# B201E.net
KiCad netlist of a schematic drawn in EAGLE
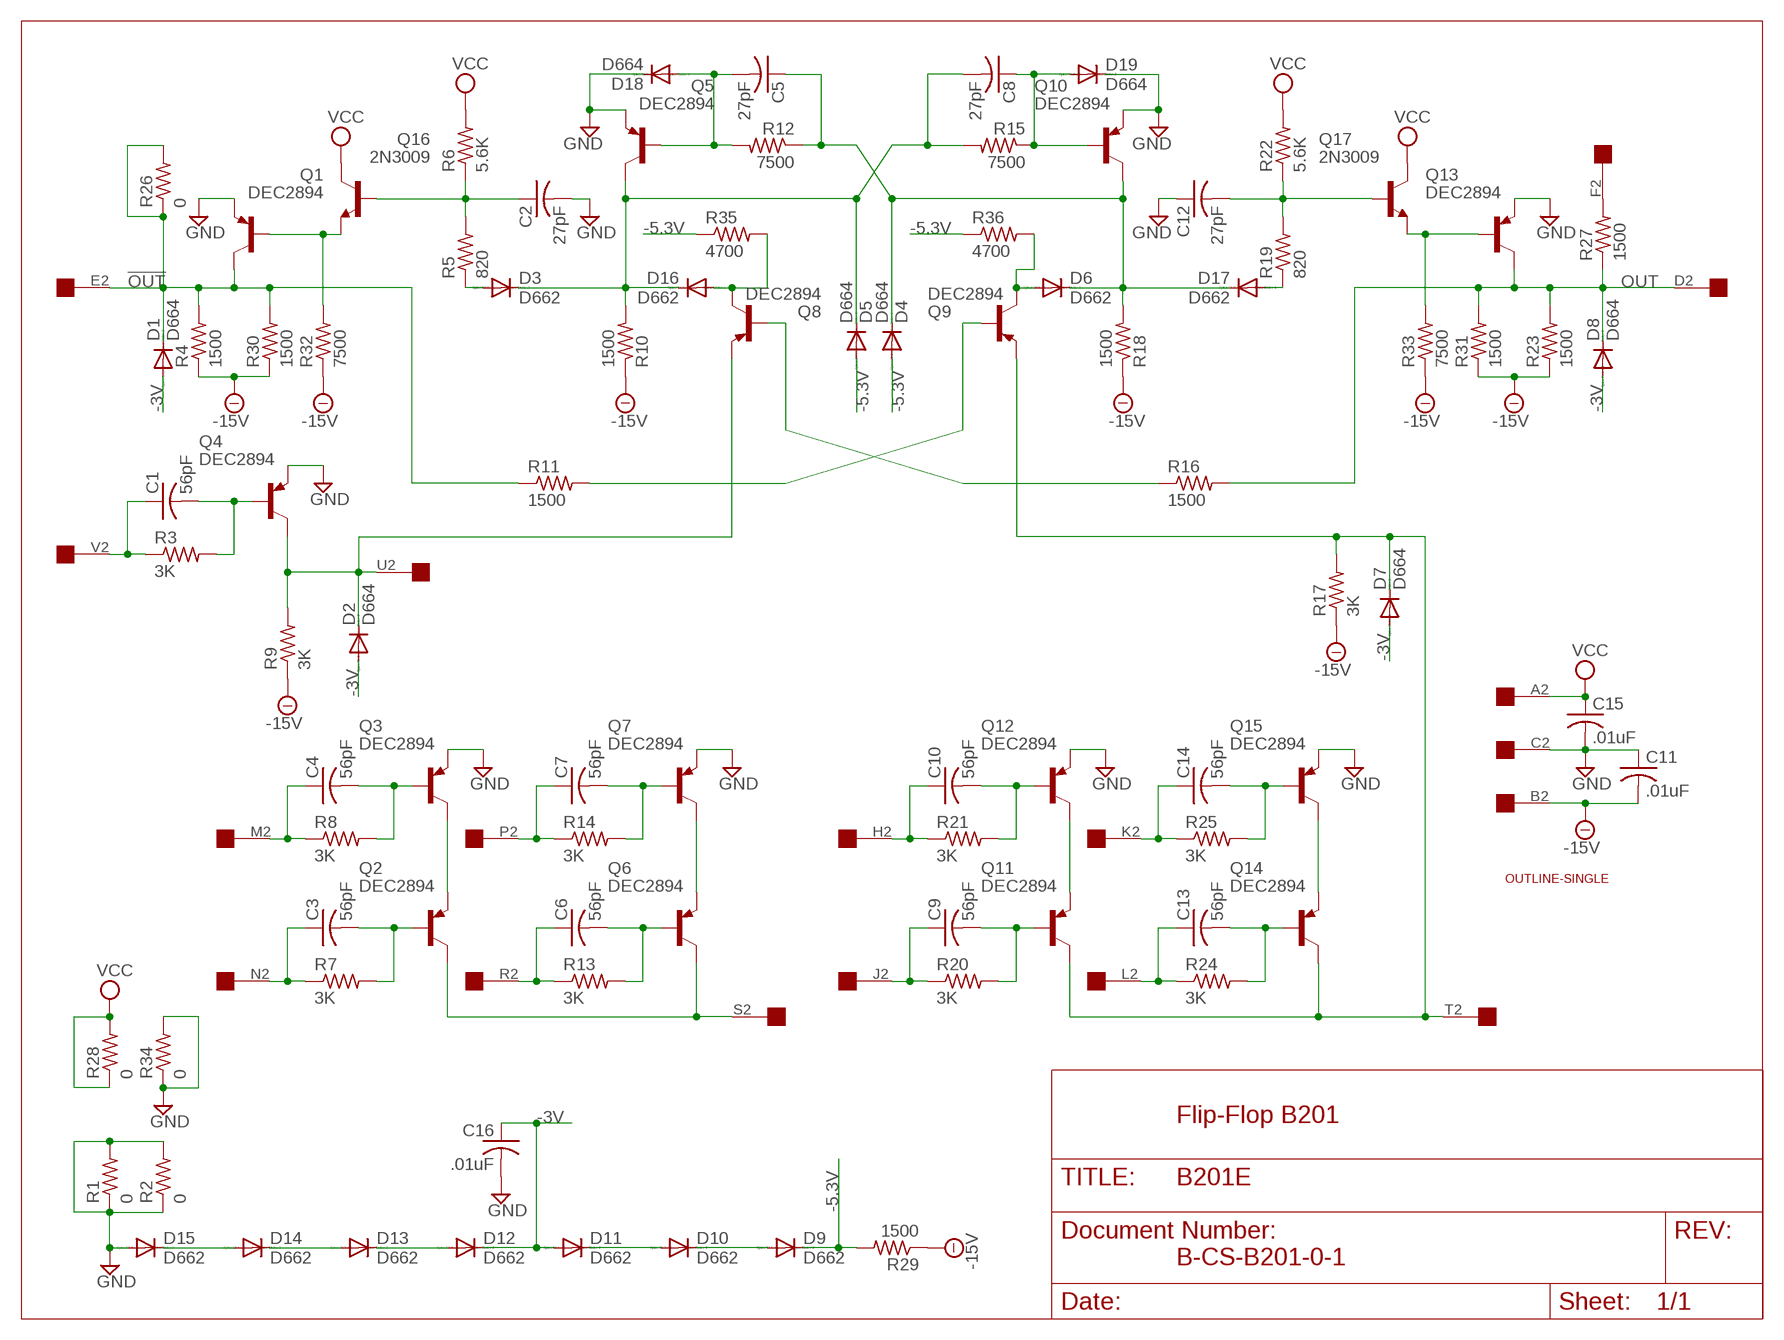
[diagram p0: schematic, sheet 1]

(export (version "E")
  (design (tool "Eeschema 10.0.6"))
  (components
    (comp (ref "C1")
      (value "56pF")
      (footprint "eagle-import:C063-025X075")
      (libsource (lib "eagle-import") (part "C-US"))
    )
    (comp (ref "C2")
      (value "27pF")
      (footprint "eagle-import:C063-025X075")
      (libsource (lib "eagle-import") (part "C-US"))
    )
    (comp (ref "C3")
      (value "56pF")
      (footprint "eagle-import:C063-025X075")
      (libsource (lib "eagle-import") (part "C-US"))
    )
    (comp (ref "C4")
      (value "56pF")
      (footprint "eagle-import:C063-025X075")
      (libsource (lib "eagle-import") (part "C-US"))
    )
    (comp (ref "C5")
      (value "27pF")
      (footprint "eagle-import:C063-025X075")
      (libsource (lib "eagle-import") (part "C-US"))
    )
    (comp (ref "C6")
      (value "56pF")
      (footprint "eagle-import:C063-025X075")
      (libsource (lib "eagle-import") (part "C-US"))
    )
    (comp (ref "C7")
      (value "56pF")
      (footprint "eagle-import:C063-025X075")
      (libsource (lib "eagle-import") (part "C-US"))
    )
    (comp (ref "C8")
      (value "27pF")
      (footprint "eagle-import:C063-025X075")
      (libsource (lib "eagle-import") (part "C-US"))
    )
    (comp (ref "C9")
      (value "56pF")
      (footprint "eagle-import:C063-025X075")
      (libsource (lib "eagle-import") (part "C-US"))
    )
    (comp (ref "C10")
      (value "56pF")
      (footprint "eagle-import:C063-025X075")
      (libsource (lib "eagle-import") (part "C-US"))
    )
    (comp (ref "C11")
      (value ".01uF")
      (footprint "eagle-import:C063-025X075")
      (libsource (lib "eagle-import") (part "C-US"))
    )
    (comp (ref "C12")
      (value "27pF")
      (footprint "eagle-import:C063-025X075")
      (libsource (lib "eagle-import") (part "C-US"))
    )
    (comp (ref "C13")
      (value "56pF")
      (footprint "eagle-import:C063-025X075")
      (libsource (lib "eagle-import") (part "C-US"))
    )
    (comp (ref "C14")
      (value "56pF")
      (footprint "eagle-import:C063-025X075")
      (libsource (lib "eagle-import") (part "C-US"))
    )
    (comp (ref "C15")
      (value ".01uF")
      (footprint "eagle-import:C063-025X075")
      (libsource (lib "eagle-import") (part "C-US"))
    )
    (comp (ref "C16")
      (value ".01uF")
      (footprint "eagle-import:C063-025X075")
      (libsource (lib "eagle-import") (part "C-US"))
    )
    (comp (ref "D1")
      (value "D664")
      (footprint "eagle-import:DO35-10")
      (libsource (lib "eagle-import") (part "DIODE-DO35-10"))
    )
    (comp (ref "D2")
      (value "D664")
      (footprint "eagle-import:DO35-10")
      (libsource (lib "eagle-import") (part "DIODE-DO35-10"))
    )
    (comp (ref "D3")
      (value "D662")
      (footprint "eagle-import:DO35-10")
      (libsource (lib "eagle-import") (part "DIODE-DO35-10"))
    )
    (comp (ref "D4")
      (value "D664")
      (footprint "eagle-import:DO35-10")
      (libsource (lib "eagle-import") (part "DIODE-DO35-10"))
    )
    (comp (ref "D5")
      (value "D664")
      (footprint "eagle-import:DO35-10")
      (libsource (lib "eagle-import") (part "DIODE-DO35-10"))
    )
    (comp (ref "D6")
      (value "D662")
      (footprint "eagle-import:DO35-10")
      (libsource (lib "eagle-import") (part "DIODE-DO35-10"))
    )
    (comp (ref "D7")
      (value "D664")
      (footprint "eagle-import:DO35-10")
      (libsource (lib "eagle-import") (part "DIODE-DO35-10"))
    )
    (comp (ref "D8")
      (value "D664")
      (footprint "eagle-import:DO35-10")
      (libsource (lib "eagle-import") (part "DIODE-DO35-10"))
    )
    (comp (ref "D9")
      (value "D662")
      (footprint "eagle-import:DO35-10")
      (libsource (lib "eagle-import") (part "DIODE-DO35-10"))
    )
    (comp (ref "D10")
      (value "D662")
      (footprint "eagle-import:DO35-10")
      (libsource (lib "eagle-import") (part "DIODE-DO35-10"))
    )
    (comp (ref "D11")
      (value "D662")
      (footprint "eagle-import:DO35-10")
      (libsource (lib "eagle-import") (part "DIODE-DO35-10"))
    )
    (comp (ref "D12")
      (value "D662")
      (footprint "eagle-import:DO35-10")
      (libsource (lib "eagle-import") (part "DIODE-DO35-10"))
    )
    (comp (ref "D13")
      (value "D662")
      (footprint "eagle-import:DO35-10")
      (libsource (lib "eagle-import") (part "DIODE-DO35-10"))
    )
    (comp (ref "D14")
      (value "D662")
      (footprint "eagle-import:DO35-10")
      (libsource (lib "eagle-import") (part "DIODE-DO35-10"))
    )
    (comp (ref "D15")
      (value "D662")
      (footprint "eagle-import:DO35-10")
      (libsource (lib "eagle-import") (part "DIODE-DO35-10"))
    )
    (comp (ref "D16")
      (value "D662")
      (footprint "eagle-import:DO35-10")
      (libsource (lib "eagle-import") (part "DIODE-DO35-10"))
    )
    (comp (ref "D17")
      (value "D662")
      (footprint "eagle-import:DO35-10")
      (libsource (lib "eagle-import") (part "DIODE-DO35-10"))
    )
    (comp (ref "D18")
      (value "D664")
      (footprint "eagle-import:DO35-10")
      (libsource (lib "eagle-import") (part "DIODE-DO35-10"))
    )
    (comp (ref "D19")
      (value "D664")
      (footprint "eagle-import:DO35-10")
      (libsource (lib "eagle-import") (part "DIODE-DO35-10"))
    )
    (comp (ref "Q1")
      (value "DEC2894")
      (footprint "eagle-import:TO5")
      (libsource (lib "eagle-import") (part "-PNP-TO5"))
    )
    (comp (ref "Q2")
      (value "DEC2894")
      (footprint "eagle-import:TO5")
      (libsource (lib "eagle-import") (part "-PNP-TO5"))
    )
    (comp (ref "Q3")
      (value "DEC2894")
      (footprint "eagle-import:TO5")
      (libsource (lib "eagle-import") (part "-PNP-TO5"))
    )
    (comp (ref "Q4")
      (value "DEC2894")
      (footprint "eagle-import:TO5")
      (libsource (lib "eagle-import") (part "-PNP-TO5"))
    )
    (comp (ref "Q5")
      (value "DEC2894")
      (footprint "eagle-import:TO5")
      (libsource (lib "eagle-import") (part "-PNP-TO5"))
    )
    (comp (ref "Q6")
      (value "DEC2894")
      (footprint "eagle-import:TO5")
      (libsource (lib "eagle-import") (part "-PNP-TO5"))
    )
    (comp (ref "Q7")
      (value "DEC2894")
      (footprint "eagle-import:TO5")
      (libsource (lib "eagle-import") (part "-PNP-TO5"))
    )
    (comp (ref "Q8")
      (value "DEC2894")
      (footprint "eagle-import:TO5")
      (libsource (lib "eagle-import") (part "-PNP-TO5"))
    )
    (comp (ref "Q9")
      (value "DEC2894")
      (footprint "eagle-import:TO5")
      (libsource (lib "eagle-import") (part "-PNP-TO5"))
    )
    (comp (ref "Q10")
      (value "DEC2894")
      (footprint "eagle-import:TO5")
      (libsource (lib "eagle-import") (part "-PNP-TO5"))
    )
    (comp (ref "Q11")
      (value "DEC2894")
      (footprint "eagle-import:TO5")
      (libsource (lib "eagle-import") (part "-PNP-TO5"))
    )
    (comp (ref "Q12")
      (value "DEC2894")
      (footprint "eagle-import:TO5")
      (libsource (lib "eagle-import") (part "-PNP-TO5"))
    )
    (comp (ref "Q13")
      (value "DEC2894")
      (footprint "eagle-import:TO5")
      (libsource (lib "eagle-import") (part "-PNP-TO5"))
    )
    (comp (ref "Q14")
      (value "DEC2894")
      (footprint "eagle-import:TO5")
      (libsource (lib "eagle-import") (part "-PNP-TO5"))
    )
    (comp (ref "Q15")
      (value "DEC2894")
      (footprint "eagle-import:TO5")
      (libsource (lib "eagle-import") (part "-PNP-TO5"))
    )
    (comp (ref "Q16")
      (value "2N3009")
      (footprint "eagle-import:TO5")
      (libsource (lib "eagle-import") (part "-NPN-TO5"))
    )
    (comp (ref "Q17")
      (value "2N3009")
      (footprint "eagle-import:TO5")
      (libsource (lib "eagle-import") (part "-NPN-TO5"))
    )
    (comp (ref "R1")
      (value "0")
      (footprint "eagle-import:0207_10")
      (libsource (lib "eagle-import") (part "R-US_0207/10"))
    )
    (comp (ref "R2")
      (value "0")
      (footprint "eagle-import:0207_10")
      (libsource (lib "eagle-import") (part "R-US_0207/10"))
    )
    (comp (ref "R3")
      (value "3K")
      (footprint "eagle-import:0207_10")
      (libsource (lib "eagle-import") (part "R-US_0207/10"))
    )
    (comp (ref "R4")
      (value "1500")
      (footprint "eagle-import:0207_10")
      (libsource (lib "eagle-import") (part "R-US_0207/10"))
    )
    (comp (ref "R5")
      (value "820")
      (footprint "eagle-import:0207_10")
      (libsource (lib "eagle-import") (part "R-US_0207/10"))
    )
    (comp (ref "R6")
      (value "5.6K")
      (footprint "eagle-import:0207_10")
      (libsource (lib "eagle-import") (part "R-US_0207/10"))
    )
    (comp (ref "R7")
      (value "3K")
      (footprint "eagle-import:0207_10")
      (libsource (lib "eagle-import") (part "R-US_0207/10"))
    )
    (comp (ref "R8")
      (value "3K")
      (footprint "eagle-import:0207_10")
      (libsource (lib "eagle-import") (part "R-US_0207/10"))
    )
    (comp (ref "R9")
      (value "3K")
      (footprint "eagle-import:0207_10")
      (libsource (lib "eagle-import") (part "R-US_0207/10"))
    )
    (comp (ref "R10")
      (value "1500")
      (footprint "eagle-import:0207_10")
      (libsource (lib "eagle-import") (part "R-US_0207/10"))
    )
    (comp (ref "R11")
      (value "1500")
      (footprint "eagle-import:0207_10")
      (libsource (lib "eagle-import") (part "R-US_0207/10"))
    )
    (comp (ref "R12")
      (value "7500")
      (footprint "eagle-import:0207_10")
      (libsource (lib "eagle-import") (part "R-US_0207/10"))
    )
    (comp (ref "R13")
      (value "3K")
      (footprint "eagle-import:0207_10")
      (libsource (lib "eagle-import") (part "R-US_0207/10"))
    )
    (comp (ref "R14")
      (value "3K")
      (footprint "eagle-import:0207_10")
      (libsource (lib "eagle-import") (part "R-US_0207/10"))
    )
    (comp (ref "R15")
      (value "7500")
      (footprint "eagle-import:0207_10")
      (libsource (lib "eagle-import") (part "R-US_0207/10"))
    )
    (comp (ref "R16")
      (value "1500")
      (footprint "eagle-import:0207_10")
      (libsource (lib "eagle-import") (part "R-US_0207/10"))
    )
    (comp (ref "R17")
      (value "3K")
      (footprint "eagle-import:0207_10")
      (libsource (lib "eagle-import") (part "R-US_0207/10"))
    )
    (comp (ref "R18")
      (value "1500")
      (footprint "eagle-import:0207_10")
      (libsource (lib "eagle-import") (part "R-US_0207/10"))
    )
    (comp (ref "R19")
      (value "820")
      (footprint "eagle-import:0207_10")
      (libsource (lib "eagle-import") (part "R-US_0207/10"))
    )
    (comp (ref "R20")
      (value "3K")
      (footprint "eagle-import:0207_10")
      (libsource (lib "eagle-import") (part "R-US_0207/10"))
    )
    (comp (ref "R21")
      (value "3K")
      (footprint "eagle-import:0207_10")
      (libsource (lib "eagle-import") (part "R-US_0207/10"))
    )
    (comp (ref "R22")
      (value "5.6K")
      (footprint "eagle-import:0207_10")
      (libsource (lib "eagle-import") (part "R-US_0207/10"))
    )
    (comp (ref "R23")
      (value "1500")
      (footprint "eagle-import:0207_10")
      (libsource (lib "eagle-import") (part "R-US_0207/10"))
    )
    (comp (ref "R24")
      (value "3K")
      (footprint "eagle-import:0207_10")
      (libsource (lib "eagle-import") (part "R-US_0207/10"))
    )
    (comp (ref "R25")
      (value "3K")
      (footprint "eagle-import:0207_10")
      (libsource (lib "eagle-import") (part "R-US_0207/10"))
    )
    (comp (ref "R26")
      (value "0")
      (footprint "eagle-import:0207_10")
      (libsource (lib "eagle-import") (part "R-US_0207/10"))
    )
    (comp (ref "R27")
      (value "1500")
      (footprint "eagle-import:0207_10")
      (libsource (lib "eagle-import") (part "R-US_0207/10"))
    )
    (comp (ref "R28")
      (value "0")
      (footprint "eagle-import:0207_10")
      (libsource (lib "eagle-import") (part "R-US_0207/10"))
    )
    (comp (ref "R29")
      (value "1500")
      (footprint "eagle-import:0207_10")
      (libsource (lib "eagle-import") (part "R-US_0207/10"))
    )
    (comp (ref "R30")
      (value "1500")
      (footprint "eagle-import:0207_10")
      (libsource (lib "eagle-import") (part "R-US_0207/10"))
    )
    (comp (ref "R31")
      (value "1500")
      (footprint "eagle-import:0207_10")
      (libsource (lib "eagle-import") (part "R-US_0207/10"))
    )
    (comp (ref "R32")
      (value "7500")
      (footprint "eagle-import:0207_10")
      (libsource (lib "eagle-import") (part "R-US_0207/10"))
    )
    (comp (ref "R33")
      (value "7500")
      (footprint "eagle-import:0207_10")
      (libsource (lib "eagle-import") (part "R-US_0207/10"))
    )
    (comp (ref "R34")
      (value "0")
      (footprint "eagle-import:0207_10")
      (libsource (lib "eagle-import") (part "R-US_0207/10"))
    )
    (comp (ref "R35")
      (value "4700")
      (footprint "eagle-import:0207_10")
      (libsource (lib "eagle-import") (part "R-US_0207/10"))
    )
    (comp (ref "R36")
      (value "4700")
      (footprint "eagle-import:0207_10")
      (libsource (lib "eagle-import") (part "R-US_0207/10"))
    )
    (comp (ref "U$1")
      (value "OUTLINE-SINGLE")
      (footprint "eagle-import:SINGLE")
      (libsource (lib "eagle-import") (part "OUTLINE-SINGLE"))
    )
    (comp (ref "U$2")
      (value "EDGE-1")
      (footprint "eagle-import:EDGE-CON1")
      (libsource (lib "eagle-import") (part "EDGE-1"))
    )
  )
  (nets
    (net (code "1") (name "-15V") (class "Default")
      (node (ref "C11") (pin "2") (pinfunction "2_2") (pintype "passive"))
      (node (ref "R10") (pin "1") (pinfunction "1_1") (pintype "passive"))
      (node (ref "R17") (pin "1") (pinfunction "1_1") (pintype "passive"))
      (node (ref "R18") (pin "1") (pinfunction "1_1") (pintype "passive"))
      (node (ref "R23") (pin "1") (pinfunction "1_1") (pintype "passive"))
      (node (ref "R29") (pin "1") (pinfunction "1_1") (pintype "passive"))
      (node (ref "R30") (pin "1") (pinfunction "1_1") (pintype "passive"))
      (node (ref "R31") (pin "1") (pinfunction "1_1") (pintype "passive"))
      (node (ref "R32") (pin "1") (pinfunction "1_1") (pintype "passive"))
      (node (ref "R33") (pin "1") (pinfunction "1_1") (pintype "passive"))
      (node (ref "R4") (pin "1") (pinfunction "1_1") (pintype "passive"))
      (node (ref "R9") (pin "1") (pinfunction "1_1") (pintype "passive"))
      (node (ref "U$2") (pin "B2") (pinfunction "1_B2") (pintype "bidirectional"))
    )
    (net (code "2") (name "/-3V") (class "Default")
      (node (ref "C16") (pin "1") (pinfunction "1_1") (pintype "passive"))
      (node (ref "D1") (pin "A") (pinfunction "A_A") (pintype "passive"))
      (node (ref "D11") (pin "A") (pinfunction "A_A") (pintype "passive"))
      (node (ref "D12") (pin "C") (pinfunction "C_C") (pintype "passive"))
      (node (ref "D2") (pin "A") (pinfunction "A_A") (pintype "passive"))
      (node (ref "D7") (pin "A") (pinfunction "A_A") (pintype "passive"))
      (node (ref "D8") (pin "A") (pinfunction "A_A") (pintype "passive"))
    )
    (net (code "3") (name "/-5.3V") (class "Default")
      (node (ref "D4") (pin "A") (pinfunction "A_A") (pintype "passive"))
      (node (ref "D5") (pin "A") (pinfunction "A_A") (pintype "passive"))
      (node (ref "D9") (pin "C") (pinfunction "C_C") (pintype "passive"))
      (node (ref "R29") (pin "2") (pinfunction "2_2") (pintype "passive"))
      (node (ref "R35") (pin "1") (pinfunction "1_1") (pintype "passive"))
      (node (ref "R36") (pin "1") (pinfunction "1_1") (pintype "passive"))
    )
    (net (code "4") (name "/OUT") (class "Default")
      (node (ref "D8") (pin "C") (pinfunction "C_C") (pintype "passive"))
      (node (ref "Q13") (pin "3") (pinfunction "C_3") (pintype "passive"))
      (node (ref "R16") (pin "2") (pinfunction "2_2") (pintype "passive"))
      (node (ref "R23") (pin "2") (pinfunction "2_2") (pintype "passive"))
      (node (ref "R27") (pin "1") (pinfunction "1_1") (pintype "passive"))
      (node (ref "R31") (pin "2") (pinfunction "2_2") (pintype "passive"))
      (node (ref "U$2") (pin "D2") (pinfunction "1_D2") (pintype "bidirectional"))
    )
    (net (code "5") (name "/~{OUT}") (class "Default")
      (node (ref "D1") (pin "C") (pinfunction "C_C") (pintype "passive"))
      (node (ref "Q1") (pin "3") (pinfunction "C_3") (pintype "passive"))
      (node (ref "R11") (pin "1") (pinfunction "1_1") (pintype "passive"))
      (node (ref "R26") (pin "1") (pinfunction "1_1") (pintype "passive"))
      (node (ref "R26") (pin "2") (pinfunction "2_2") (pintype "passive"))
      (node (ref "R30") (pin "2") (pinfunction "2_2") (pintype "passive"))
      (node (ref "R4") (pin "2") (pinfunction "2_2") (pintype "passive"))
      (node (ref "U$2") (pin "E2") (pinfunction "1_E2") (pintype "bidirectional"))
    )
    (net (code "6") (name "GND") (class "Default")
      (node (ref "C11") (pin "1") (pinfunction "1_1") (pintype "passive"))
      (node (ref "C12") (pin "1") (pinfunction "1_1") (pintype "passive"))
      (node (ref "C15") (pin "2") (pinfunction "2_2") (pintype "passive"))
      (node (ref "C16") (pin "2") (pinfunction "2_2") (pintype "passive"))
      (node (ref "C2") (pin "2") (pinfunction "2_2") (pintype "passive"))
      (node (ref "D15") (pin "A") (pinfunction "A_A") (pintype "passive"))
      (node (ref "D18") (pin "C") (pinfunction "C_C") (pintype "passive"))
      (node (ref "D19") (pin "C") (pinfunction "C_C") (pintype "passive"))
      (node (ref "Q1") (pin "1") (pinfunction "E_1") (pintype "passive"))
      (node (ref "Q10") (pin "1") (pinfunction "E_1") (pintype "passive"))
      (node (ref "Q12") (pin "1") (pinfunction "E_1") (pintype "passive"))
      (node (ref "Q13") (pin "1") (pinfunction "E_1") (pintype "passive"))
      (node (ref "Q15") (pin "1") (pinfunction "E_1") (pintype "passive"))
      (node (ref "Q3") (pin "1") (pinfunction "E_1") (pintype "passive"))
      (node (ref "Q4") (pin "1") (pinfunction "E_1") (pintype "passive"))
      (node (ref "Q5") (pin "1") (pinfunction "E_1") (pintype "passive"))
      (node (ref "Q7") (pin "1") (pinfunction "E_1") (pintype "passive"))
      (node (ref "R1") (pin "1") (pinfunction "1_1") (pintype "passive"))
      (node (ref "R1") (pin "2") (pinfunction "2_2") (pintype "passive"))
      (node (ref "R2") (pin "1") (pinfunction "1_1") (pintype "passive"))
      (node (ref "R2") (pin "2") (pinfunction "2_2") (pintype "passive"))
      (node (ref "R34") (pin "1") (pinfunction "1_1") (pintype "passive"))
      (node (ref "R34") (pin "2") (pinfunction "2_2") (pintype "passive"))
      (node (ref "U$2") (pin "C2") (pinfunction "1_C2") (pintype "bidirectional"))
    )
    (net (code "7") (name "Net-(D3-PadA)") (class "Default")
      (node (ref "D3") (pin "A") (pinfunction "A_A") (pintype "passive"))
      (node (ref "R5") (pin "1") (pinfunction "1_1") (pintype "passive"))
    )
    (net (code "8") (name "Net-(D10-PadA)") (class "Default")
      (node (ref "D10") (pin "A") (pinfunction "A_A") (pintype "passive"))
      (node (ref "D11") (pin "C") (pinfunction "C_C") (pintype "passive"))
    )
    (net (code "9") (name "Net-(D10-PadC)") (class "Default")
      (node (ref "D10") (pin "C") (pinfunction "C_C") (pintype "passive"))
      (node (ref "D9") (pin "A") (pinfunction "A_A") (pintype "passive"))
    )
    (net (code "10") (name "Net-(D12-PadA)") (class "Default")
      (node (ref "D12") (pin "A") (pinfunction "A_A") (pintype "passive"))
      (node (ref "D13") (pin "C") (pinfunction "C_C") (pintype "passive"))
    )
    (net (code "11") (name "Net-(D13-PadA)") (class "Default")
      (node (ref "D13") (pin "A") (pinfunction "A_A") (pintype "passive"))
      (node (ref "D14") (pin "C") (pinfunction "C_C") (pintype "passive"))
    )
    (net (code "12") (name "Net-(D14-PadA)") (class "Default")
      (node (ref "D14") (pin "A") (pinfunction "A_A") (pintype "passive"))
      (node (ref "D15") (pin "C") (pinfunction "C_C") (pintype "passive"))
    )
    (net (code "13") (name "Net-(D17-PadA)") (class "Default")
      (node (ref "D17") (pin "A") (pinfunction "A_A") (pintype "passive"))
      (node (ref "R19") (pin "1") (pinfunction "1_1") (pintype "passive"))
    )
    (net (code "14") (name "Net-(Q1-B)") (class "Default")
      (node (ref "Q1") (pin "2") (pinfunction "B_2") (pintype "passive"))
      (node (ref "Q16") (pin "1") (pinfunction "E_1") (pintype "passive"))
      (node (ref "R32") (pin "2") (pinfunction "2_2") (pintype "passive"))
    )
    (net (code "15") (name "Net-(Q2-B)") (class "Default")
      (node (ref "C3") (pin "2") (pinfunction "2_2") (pintype "passive"))
      (node (ref "Q2") (pin "2") (pinfunction "B_2") (pintype "passive"))
      (node (ref "R7") (pin "2") (pinfunction "2_2") (pintype "passive"))
    )
    (net (code "16") (name "Net-(Q2-C)") (class "Default")
      (node (ref "Q2") (pin "3") (pinfunction "C_3") (pintype "passive"))
      (node (ref "Q6") (pin "3") (pinfunction "C_3") (pintype "passive"))
      (node (ref "U$2") (pin "S2") (pinfunction "1_S2") (pintype "bidirectional"))
    )
    (net (code "17") (name "Net-(Q2-E)") (class "Default")
      (node (ref "Q2") (pin "1") (pinfunction "E_1") (pintype "passive"))
      (node (ref "Q3") (pin "3") (pinfunction "C_3") (pintype "passive"))
    )
    (net (code "18") (name "Net-(Q3-B)") (class "Default")
      (node (ref "C4") (pin "2") (pinfunction "2_2") (pintype "passive"))
      (node (ref "Q3") (pin "2") (pinfunction "B_2") (pintype "passive"))
      (node (ref "R8") (pin "2") (pinfunction "2_2") (pintype "passive"))
    )
    (net (code "19") (name "Net-(Q4-B)") (class "Default")
      (node (ref "C1") (pin "2") (pinfunction "2_2") (pintype "passive"))
      (node (ref "Q4") (pin "2") (pinfunction "B_2") (pintype "passive"))
      (node (ref "R3") (pin "2") (pinfunction "2_2") (pintype "passive"))
    )
    (net (code "20") (name "Net-(Q4-C)") (class "Default")
      (node (ref "D2") (pin "C") (pinfunction "C_C") (pintype "passive"))
      (node (ref "Q4") (pin "3") (pinfunction "C_3") (pintype "passive"))
      (node (ref "Q8") (pin "1") (pinfunction "E_1") (pintype "passive"))
      (node (ref "R9") (pin "2") (pinfunction "2_2") (pintype "passive"))
      (node (ref "U$2") (pin "U2") (pinfunction "1_U2") (pintype "bidirectional"))
    )
    (net (code "21") (name "Net-(Q5-B)") (class "Default")
      (node (ref "C5") (pin "2") (pinfunction "2_2") (pintype "passive"))
      (node (ref "D18") (pin "A") (pinfunction "A_A") (pintype "passive"))
      (node (ref "Q5") (pin "2") (pinfunction "B_2") (pintype "passive"))
      (node (ref "R12") (pin "2") (pinfunction "2_2") (pintype "passive"))
    )
    (net (code "22") (name "Net-(Q5-C)") (class "Default")
      (node (ref "C8") (pin "2") (pinfunction "2_2") (pintype "passive"))
      (node (ref "D16") (pin "C") (pinfunction "C_C") (pintype "passive"))
      (node (ref "D3") (pin "C") (pinfunction "C_C") (pintype "passive"))
      (node (ref "D5") (pin "C") (pinfunction "C_C") (pintype "passive"))
      (node (ref "Q5") (pin "3") (pinfunction "C_3") (pintype "passive"))
      (node (ref "R10") (pin "2") (pinfunction "2_2") (pintype "passive"))
      (node (ref "R15") (pin "2") (pinfunction "2_2") (pintype "passive"))
    )
    (net (code "23") (name "Net-(Q6-B)") (class "Default")
      (node (ref "C6") (pin "2") (pinfunction "2_2") (pintype "passive"))
      (node (ref "Q6") (pin "2") (pinfunction "B_2") (pintype "passive"))
      (node (ref "R13") (pin "2") (pinfunction "2_2") (pintype "passive"))
    )
    (net (code "24") (name "Net-(Q6-E)") (class "Default")
      (node (ref "Q6") (pin "1") (pinfunction "E_1") (pintype "passive"))
      (node (ref "Q7") (pin "3") (pinfunction "C_3") (pintype "passive"))
    )
    (net (code "25") (name "Net-(Q7-B)") (class "Default")
      (node (ref "C7") (pin "2") (pinfunction "2_2") (pintype "passive"))
      (node (ref "Q7") (pin "2") (pinfunction "B_2") (pintype "passive"))
      (node (ref "R14") (pin "2") (pinfunction "2_2") (pintype "passive"))
    )
    (net (code "26") (name "Net-(Q8-B)") (class "Default")
      (node (ref "Q8") (pin "2") (pinfunction "B_2") (pintype "passive"))
      (node (ref "R16") (pin "1") (pinfunction "1_1") (pintype "passive"))
    )
    (net (code "27") (name "Net-(Q8-C)") (class "Default")
      (node (ref "D16") (pin "A") (pinfunction "A_A") (pintype "passive"))
      (node (ref "Q8") (pin "3") (pinfunction "C_3") (pintype "passive"))
      (node (ref "R35") (pin "2") (pinfunction "2_2") (pintype "passive"))
    )
    (net (code "28") (name "Net-(Q9-B)") (class "Default")
      (node (ref "Q9") (pin "2") (pinfunction "B_2") (pintype "passive"))
      (node (ref "R11") (pin "2") (pinfunction "2_2") (pintype "passive"))
    )
    (net (code "29") (name "Net-(Q9-C)") (class "Default")
      (node (ref "D6") (pin "A") (pinfunction "A_A") (pintype "passive"))
      (node (ref "Q9") (pin "3") (pinfunction "C_3") (pintype "passive"))
      (node (ref "R36") (pin "2") (pinfunction "2_2") (pintype "passive"))
    )
    (net (code "30") (name "Net-(Q10-B)") (class "Default")
      (node (ref "C8") (pin "1") (pinfunction "1_1") (pintype "passive"))
      (node (ref "D19") (pin "A") (pinfunction "A_A") (pintype "passive"))
      (node (ref "Q10") (pin "2") (pinfunction "B_2") (pintype "passive"))
      (node (ref "R15") (pin "1") (pinfunction "1_1") (pintype "passive"))
    )
    (net (code "31") (name "Net-(Q10-C)") (class "Default")
      (node (ref "C5") (pin "1") (pinfunction "1_1") (pintype "passive"))
      (node (ref "D17") (pin "C") (pinfunction "C_C") (pintype "passive"))
      (node (ref "D4") (pin "C") (pinfunction "C_C") (pintype "passive"))
      (node (ref "D6") (pin "C") (pinfunction "C_C") (pintype "passive"))
      (node (ref "Q10") (pin "3") (pinfunction "C_3") (pintype "passive"))
      (node (ref "R12") (pin "1") (pinfunction "1_1") (pintype "passive"))
      (node (ref "R18") (pin "2") (pinfunction "2_2") (pintype "passive"))
    )
    (net (code "32") (name "Net-(Q11-B)") (class "Default")
      (node (ref "C9") (pin "2") (pinfunction "2_2") (pintype "passive"))
      (node (ref "Q11") (pin "2") (pinfunction "B_2") (pintype "passive"))
      (node (ref "R20") (pin "2") (pinfunction "2_2") (pintype "passive"))
    )
    (net (code "33") (name "Net-(Q11-C)") (class "Default")
      (node (ref "D7") (pin "C") (pinfunction "C_C") (pintype "passive"))
      (node (ref "Q11") (pin "3") (pinfunction "C_3") (pintype "passive"))
      (node (ref "Q14") (pin "3") (pinfunction "C_3") (pintype "passive"))
      (node (ref "Q9") (pin "1") (pinfunction "E_1") (pintype "passive"))
      (node (ref "R17") (pin "2") (pinfunction "2_2") (pintype "passive"))
      (node (ref "U$2") (pin "T2") (pinfunction "1_T2") (pintype "bidirectional"))
    )
    (net (code "34") (name "Net-(Q11-E)") (class "Default")
      (node (ref "Q11") (pin "1") (pinfunction "E_1") (pintype "passive"))
      (node (ref "Q12") (pin "3") (pinfunction "C_3") (pintype "passive"))
    )
    (net (code "35") (name "Net-(Q12-B)") (class "Default")
      (node (ref "C10") (pin "2") (pinfunction "2_2") (pintype "passive"))
      (node (ref "Q12") (pin "2") (pinfunction "B_2") (pintype "passive"))
      (node (ref "R21") (pin "2") (pinfunction "2_2") (pintype "passive"))
    )
    (net (code "36") (name "Net-(Q13-B)") (class "Default")
      (node (ref "Q13") (pin "2") (pinfunction "B_2") (pintype "passive"))
      (node (ref "Q17") (pin "1") (pinfunction "E_1") (pintype "passive"))
      (node (ref "R33") (pin "2") (pinfunction "2_2") (pintype "passive"))
    )
    (net (code "37") (name "Net-(Q14-B)") (class "Default")
      (node (ref "C13") (pin "2") (pinfunction "2_2") (pintype "passive"))
      (node (ref "Q14") (pin "2") (pinfunction "B_2") (pintype "passive"))
      (node (ref "R24") (pin "2") (pinfunction "2_2") (pintype "passive"))
    )
    (net (code "38") (name "Net-(Q14-E)") (class "Default")
      (node (ref "Q14") (pin "1") (pinfunction "E_1") (pintype "passive"))
      (node (ref "Q15") (pin "3") (pinfunction "C_3") (pintype "passive"))
    )
    (net (code "39") (name "Net-(Q15-B)") (class "Default")
      (node (ref "C14") (pin "2") (pinfunction "2_2") (pintype "passive"))
      (node (ref "Q15") (pin "2") (pinfunction "B_2") (pintype "passive"))
      (node (ref "R25") (pin "2") (pinfunction "2_2") (pintype "passive"))
    )
    (net (code "40") (name "Net-(Q16-B)") (class "Default")
      (node (ref "C2") (pin "1") (pinfunction "1_1") (pintype "passive"))
      (node (ref "Q16") (pin "2") (pinfunction "B_2") (pintype "passive"))
      (node (ref "R5") (pin "2") (pinfunction "2_2") (pintype "passive"))
      (node (ref "R6") (pin "1") (pinfunction "1_1") (pintype "passive"))
    )
    (net (code "41") (name "Net-(Q17-B)") (class "Default")
      (node (ref "C12") (pin "2") (pinfunction "2_2") (pintype "passive"))
      (node (ref "Q17") (pin "2") (pinfunction "B_2") (pintype "passive"))
      (node (ref "R19") (pin "2") (pinfunction "2_2") (pintype "passive"))
      (node (ref "R22") (pin "1") (pinfunction "1_1") (pintype "passive"))
    )
    (net (code "42") (name "Net-(U$2F-1)") (class "Default")
      (node (ref "R27") (pin "2") (pinfunction "2_2") (pintype "passive"))
      (node (ref "U$2") (pin "F2") (pinfunction "1_F2") (pintype "bidirectional"))
    )
    (net (code "43") (name "Net-(U$2G-1)") (class "Default")
      (node (ref "C10") (pin "1") (pinfunction "1_1") (pintype "passive"))
      (node (ref "R21") (pin "1") (pinfunction "1_1") (pintype "passive"))
      (node (ref "U$2") (pin "H2") (pinfunction "1_H2") (pintype "bidirectional"))
    )
    (net (code "44") (name "Net-(U$2H-1)") (class "Default")
      (node (ref "C9") (pin "1") (pinfunction "1_1") (pintype "passive"))
      (node (ref "R20") (pin "1") (pinfunction "1_1") (pintype "passive"))
      (node (ref "U$2") (pin "J2") (pinfunction "1_J2") (pintype "bidirectional"))
    )
    (net (code "45") (name "Net-(U$2I-1)") (class "Default")
      (node (ref "C14") (pin "1") (pinfunction "1_1") (pintype "passive"))
      (node (ref "R25") (pin "1") (pinfunction "1_1") (pintype "passive"))
      (node (ref "U$2") (pin "K2") (pinfunction "1_K2") (pintype "bidirectional"))
    )
    (net (code "46") (name "Net-(U$2J-1)") (class "Default")
      (node (ref "C13") (pin "1") (pinfunction "1_1") (pintype "passive"))
      (node (ref "R24") (pin "1") (pinfunction "1_1") (pintype "passive"))
      (node (ref "U$2") (pin "L2") (pinfunction "1_L2") (pintype "bidirectional"))
    )
    (net (code "47") (name "Net-(U$2K-1)") (class "Default")
      (node (ref "C4") (pin "1") (pinfunction "1_1") (pintype "passive"))
      (node (ref "R8") (pin "1") (pinfunction "1_1") (pintype "passive"))
      (node (ref "U$2") (pin "M2") (pinfunction "1_M2") (pintype "bidirectional"))
    )
    (net (code "48") (name "Net-(U$2L-1)") (class "Default")
      (node (ref "C3") (pin "1") (pinfunction "1_1") (pintype "passive"))
      (node (ref "R7") (pin "1") (pinfunction "1_1") (pintype "passive"))
      (node (ref "U$2") (pin "N2") (pinfunction "1_N2") (pintype "bidirectional"))
    )
    (net (code "49") (name "Net-(U$2M-1)") (class "Default")
      (node (ref "C7") (pin "1") (pinfunction "1_1") (pintype "passive"))
      (node (ref "R14") (pin "1") (pinfunction "1_1") (pintype "passive"))
      (node (ref "U$2") (pin "P2") (pinfunction "1_P2") (pintype "bidirectional"))
    )
    (net (code "50") (name "Net-(U$2N-1)") (class "Default")
      (node (ref "C6") (pin "1") (pinfunction "1_1") (pintype "passive"))
      (node (ref "R13") (pin "1") (pinfunction "1_1") (pintype "passive"))
      (node (ref "U$2") (pin "R2") (pinfunction "1_R2") (pintype "bidirectional"))
    )
    (net (code "51") (name "Net-(U$2R-1)") (class "Default")
      (node (ref "C1") (pin "1") (pinfunction "1_1") (pintype "passive"))
      (node (ref "R3") (pin "1") (pinfunction "1_1") (pintype "passive"))
      (node (ref "U$2") (pin "V2") (pinfunction "1_V2") (pintype "bidirectional"))
    )
    (net (code "52") (name "VCC") (class "Default")
      (node (ref "C15") (pin "1") (pinfunction "1_1") (pintype "passive"))
      (node (ref "Q16") (pin "3") (pinfunction "C_3") (pintype "passive"))
      (node (ref "Q17") (pin "3") (pinfunction "C_3") (pintype "passive"))
      (node (ref "R22") (pin "2") (pinfunction "2_2") (pintype "passive"))
      (node (ref "R28") (pin "1") (pinfunction "1_1") (pintype "passive"))
      (node (ref "R28") (pin "2") (pinfunction "2_2") (pintype "passive"))
      (node (ref "R6") (pin "2") (pinfunction "2_2") (pintype "passive"))
      (node (ref "U$2") (pin "A2") (pinfunction "1_A2") (pintype "bidirectional"))
    )
  )
)
